# LDO_Design_Block.net
KiCad netlist of a schematic drawn in EAGLE
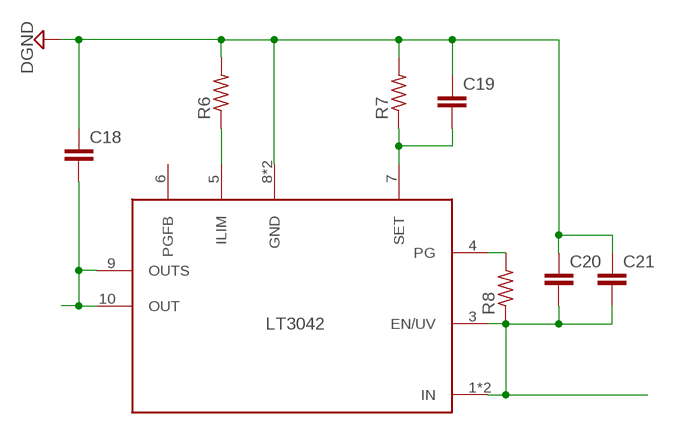
[diagram p0: schematic, sheet 1]

(export (version "E")
  (design (tool "Eeschema 10.0.6"))
  (components
    (comp (ref "C18")
      (value "C-EUC0805K")
      (footprint "eagle-import:C0805K")
      (libsource (lib "eagle-import") (part "C-EUC0805K"))
    )
    (comp (ref "C19")
      (value "C-EUC1206K")
      (footprint "eagle-import:C1206K")
      (libsource (lib "eagle-import") (part "C-EUC1206K"))
    )
    (comp (ref "C20")
      (value "C-EUC0805K")
      (footprint "eagle-import:C0805K")
      (libsource (lib "eagle-import") (part "C-EUC0805K"))
    )
    (comp (ref "C21")
      (value "C-EUC0805K")
      (footprint "eagle-import:C0805K")
      (libsource (lib "eagle-import") (part "C-EUC0805K"))
    )
    (comp (ref "LDO6")
      (value "LT3042")
      (footprint "eagle-import:SOP50P490X110-11N")
      (fields
        (field (name "MANUFACTURER_PART_NUMBER") "LT3042EMSE#PBF")
        (field (name "MOUSER_PART_NUMBER") "584-LT3042EMSE#PBF")
      )
      (libsource (lib "eagle-import") (part "LT3042"))
    )
    (comp (ref "R6")
      (value "R-US_R0805")
      (footprint "eagle-import:R0805")
      (libsource (lib "eagle-import") (part "R-US_R0805"))
    )
    (comp (ref "R7")
      (value "R-US_R0805")
      (footprint "eagle-import:R0805")
      (libsource (lib "eagle-import") (part "R-US_R0805"))
    )
    (comp (ref "R8")
      (value "R-US_R0805")
      (footprint "eagle-import:R0805")
      (libsource (lib "eagle-import") (part "R-US_R0805"))
    )
  )
  (nets
    (net (code "1") (name "DGND") (class "Default")
      (node (ref "C18") (pin "1") (pinfunction "1_1") (pintype "passive"))
      (node (ref "C19") (pin "1") (pinfunction "1_1") (pintype "passive"))
      (node (ref "C20") (pin "1") (pinfunction "1_1") (pintype "passive"))
      (node (ref "C21") (pin "1") (pinfunction "1_1") (pintype "passive"))
      (node (ref "LDO6") (pin "11") (pinfunction "GND_11") (pintype "bidirectional"))
      (node (ref "LDO6") (pin "8") (pinfunction "GND_8") (pintype "bidirectional"))
      (node (ref "R6") (pin "2") (pinfunction "2_2") (pintype "passive"))
      (node (ref "R7") (pin "2") (pinfunction "2_2") (pintype "passive"))
    )
    (net (code "2") (name "Net-(LDO6-EN{slash}UV)") (class "Default")
      (node (ref "C20") (pin "2") (pinfunction "2_2") (pintype "passive"))
      (node (ref "C21") (pin "2") (pinfunction "2_2") (pintype "passive"))
      (node (ref "LDO6") (pin "1") (pinfunction "IN_1") (pintype "bidirectional"))
      (node (ref "LDO6") (pin "2") (pinfunction "IN_2") (pintype "bidirectional"))
      (node (ref "LDO6") (pin "3") (pinfunction "EN/UV_3") (pintype "bidirectional"))
      (node (ref "R8") (pin "1") (pinfunction "1_1") (pintype "passive"))
    )
    (net (code "3") (name "Net-(LDO6-ILIM)") (class "Default")
      (node (ref "LDO6") (pin "5") (pinfunction "ILIM_5") (pintype "bidirectional"))
      (node (ref "R6") (pin "1") (pinfunction "1_1") (pintype "passive"))
    )
    (net (code "4") (name "Net-(LDO6-OUT)") (class "Default")
      (node (ref "C18") (pin "2") (pinfunction "2_2") (pintype "passive"))
      (node (ref "LDO6") (pin "10") (pinfunction "OUT_10") (pintype "bidirectional"))
      (node (ref "LDO6") (pin "9") (pinfunction "OUTS_9") (pintype "bidirectional"))
    )
    (net (code "5") (name "Net-(LDO6-PG)") (class "Default")
      (node (ref "LDO6") (pin "4") (pinfunction "PG_4") (pintype "bidirectional"))
      (node (ref "R8") (pin "2") (pinfunction "2_2") (pintype "passive"))
    )
    (net (code "6") (name "Net-(LDO6-SET)") (class "Default")
      (node (ref "C19") (pin "2") (pinfunction "2_2") (pintype "passive"))
      (node (ref "LDO6") (pin "7") (pinfunction "SET_7") (pintype "bidirectional"))
      (node (ref "R7") (pin "1") (pinfunction "1_1") (pintype "passive"))
    )
    (net (code "7") (name "unconnected-(LDO6-PGFB-Pad6)") (class "Default")
      (node (ref "LDO6") (pin "6") (pinfunction "PGFB_6") (pintype "bidirectional"))
    )
  )
)
